# RFBoardLayoutGen0_v03_2JK2.net
KiCad netlist of a schematic drawn in EAGLE
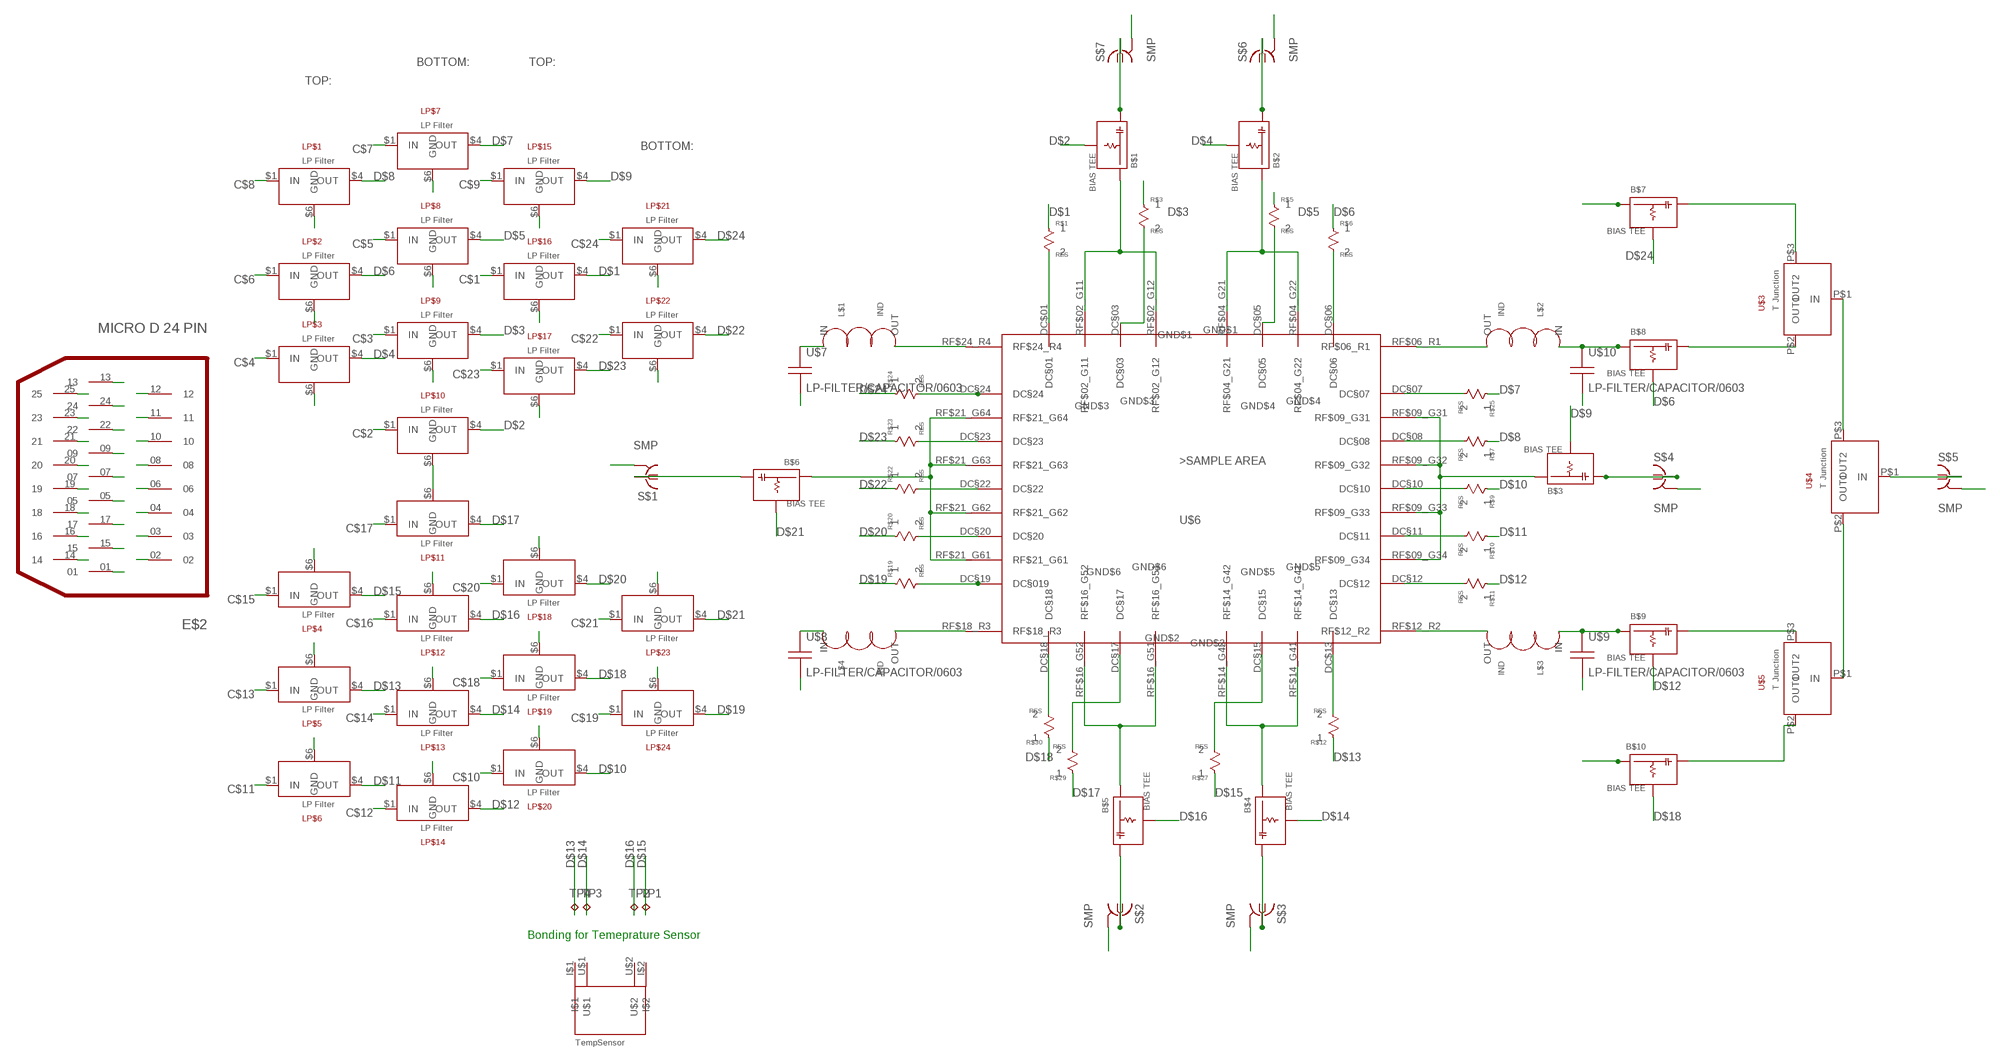
[diagram p0: schematic, sheet 1, part 1 of 2]
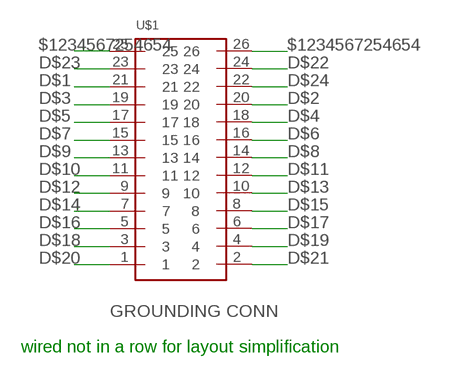
[diagram p1: schematic, sheet 1, part 2 of 2]

(export (version "E")
  (design (tool "Eeschema 10.0.6"))
  (components
    (comp (ref "B$1")
      (value "BIASTEEDOWN")
      (footprint "eagle-import:BIAS_TEE_DOWN_0603")
      (libsource (lib "eagle-import") (part "BIASTEEDOWN"))
    )
    (comp (ref "B$2")
      (value "BIASTEEUP")
      (footprint "eagle-import:BIAS_TEE_UP_0603")
      (libsource (lib "eagle-import") (part "BIASTEEUP"))
    )
    (comp (ref "B$3")
      (value "BIASTEEDOWN")
      (footprint "eagle-import:BIAS_TEE_DOWN_0603")
      (libsource (lib "eagle-import") (part "BIASTEEDOWN"))
    )
    (comp (ref "B$4")
      (value "BIASTEEDOWN")
      (footprint "eagle-import:BIAS_TEE_DOWN_0603")
      (libsource (lib "eagle-import") (part "BIASTEEDOWN"))
    )
    (comp (ref "B$5")
      (value "BIASTEEUP")
      (footprint "eagle-import:BIAS_TEE_UP_0603")
      (libsource (lib "eagle-import") (part "BIASTEEUP"))
    )
    (comp (ref "B$6")
      (value "BIASTEEDOWN")
      (footprint "eagle-import:BIAS_TEE_DOWN_0603")
      (libsource (lib "eagle-import") (part "BIASTEEDOWN"))
    )
    (comp (ref "B$7")
      (value "BIASTEEUP")
      (footprint "eagle-import:BIAS_TEE_UP_0603")
      (libsource (lib "eagle-import") (part "BIASTEEUP"))
    )
    (comp (ref "B$8")
      (value "BIASTEEDOWN")
      (footprint "eagle-import:BIAS_TEE_DOWN_0603")
      (libsource (lib "eagle-import") (part "BIASTEEDOWN"))
    )
    (comp (ref "B$9")
      (value "BIASTEEUP")
      (footprint "eagle-import:BIAS_TEE_UP_0603")
      (libsource (lib "eagle-import") (part "BIASTEEUP"))
    )
    (comp (ref "B$10")
      (value "BIASTEEDOWN")
      (footprint "eagle-import:BIAS_TEE_DOWN_0603")
      (libsource (lib "eagle-import") (part "BIASTEEDOWN"))
    )
    (comp (ref "E$2")
      (value "25_SOCKET_M83513(13-DPINOUT2")
      (footprint "eagle-import:25_SOCKET_M83513_13-D_V2")
      (libsource (lib "eagle-import") (part "25_SOCKET_M83513(13-DPINOUT2"))
    )
    (comp (ref "L$1")
      (value "L_MATCH")
      (footprint "eagle-import:L_MATCH")
      (libsource (lib "eagle-import") (part "L_MATCH"))
    )
    (comp (ref "L$2")
      (value "L_MATCH")
      (footprint "eagle-import:L_MATCH")
      (libsource (lib "eagle-import") (part "L_MATCH"))
    )
    (comp (ref "L$3")
      (value "L_MATCH")
      (footprint "eagle-import:L_MATCH")
      (libsource (lib "eagle-import") (part "L_MATCH"))
    )
    (comp (ref "L$4")
      (value "L_MATCH")
      (footprint "eagle-import:L_MATCH")
      (libsource (lib "eagle-import") (part "L_MATCH"))
    )
    (comp (ref "LP$1")
      (value "LP-FILTER/1-STAGETOP")
      (footprint "eagle-import:LP-FILTER_1_STAGE_OS_0603_TOP")
      (libsource (lib "eagle-import") (part "LP-FILTER/1-STAGETOP"))
    )
    (comp (ref "LP$2")
      (value "LP-FILTER/1-STAGETOP")
      (footprint "eagle-import:LP-FILTER_1_STAGE_OS_0603_TOP")
      (libsource (lib "eagle-import") (part "LP-FILTER/1-STAGETOP"))
    )
    (comp (ref "LP$3")
      (value "LP-FILTER/1-STAGETOP")
      (footprint "eagle-import:LP-FILTER_1_STAGE_OS_0603_TOP")
      (libsource (lib "eagle-import") (part "LP-FILTER/1-STAGETOP"))
    )
    (comp (ref "LP$4")
      (value "LP-FILTER/1-STAGETOP")
      (footprint "eagle-import:LP-FILTER_1_STAGE_OS_0603_TOP")
      (libsource (lib "eagle-import") (part "LP-FILTER/1-STAGETOP"))
    )
    (comp (ref "LP$5")
      (value "LP-FILTER/1-STAGETOP")
      (footprint "eagle-import:LP-FILTER_1_STAGE_OS_0603_TOP")
      (libsource (lib "eagle-import") (part "LP-FILTER/1-STAGETOP"))
    )
    (comp (ref "LP$6")
      (value "LP-FILTER/1-STAGETOP")
      (footprint "eagle-import:LP-FILTER_1_STAGE_OS_0603_TOP")
      (libsource (lib "eagle-import") (part "LP-FILTER/1-STAGETOP"))
    )
    (comp (ref "LP$7")
      (value "LP-FILTER/1-STAGEBOT")
      (footprint "eagle-import:LP-FILTER_1_STAGE_OS_0603_BOTTOM")
      (libsource (lib "eagle-import") (part "LP-FILTER/1-STAGEBOT"))
    )
    (comp (ref "LP$8")
      (value "LP-FILTER/1-STAGEBOT")
      (footprint "eagle-import:LP-FILTER_1_STAGE_OS_0603_BOTTOM")
      (libsource (lib "eagle-import") (part "LP-FILTER/1-STAGEBOT"))
    )
    (comp (ref "LP$9")
      (value "LP-FILTER/1-STAGEBOT")
      (footprint "eagle-import:LP-FILTER_1_STAGE_OS_0603_BOTTOM")
      (libsource (lib "eagle-import") (part "LP-FILTER/1-STAGEBOT"))
    )
    (comp (ref "LP$10")
      (value "LP-FILTER/1-STAGEBOT")
      (footprint "eagle-import:LP-FILTER_1_STAGE_OS_0603_BOTTOM")
      (libsource (lib "eagle-import") (part "LP-FILTER/1-STAGEBOT"))
    )
    (comp (ref "LP$11")
      (value "LP-FILTER/1-STAGEBOT")
      (footprint "eagle-import:LP-FILTER_1_STAGE_OS_0603_BOTTOM")
      (libsource (lib "eagle-import") (part "LP-FILTER/1-STAGEBOT"))
    )
    (comp (ref "LP$12")
      (value "LP-FILTER/1-STAGEBOT")
      (footprint "eagle-import:LP-FILTER_1_STAGE_OS_0603_BOTTOM")
      (libsource (lib "eagle-import") (part "LP-FILTER/1-STAGEBOT"))
    )
    (comp (ref "LP$13")
      (value "LP-FILTER/1-STAGEBOT")
      (footprint "eagle-import:LP-FILTER_1_STAGE_OS_0603_BOTTOM")
      (libsource (lib "eagle-import") (part "LP-FILTER/1-STAGEBOT"))
    )
    (comp (ref "LP$14")
      (value "LP-FILTER/1-STAGEBOT")
      (footprint "eagle-import:LP-FILTER_1_STAGE_OS_0603_BOTTOM")
      (libsource (lib "eagle-import") (part "LP-FILTER/1-STAGEBOT"))
    )
    (comp (ref "LP$15")
      (value "LP-FILTER/1-STAGETOP")
      (footprint "eagle-import:LP-FILTER_1_STAGE_OS_0603_TOP")
      (libsource (lib "eagle-import") (part "LP-FILTER/1-STAGETOP"))
    )
    (comp (ref "LP$16")
      (value "LP-FILTER/1-STAGETOP")
      (footprint "eagle-import:LP-FILTER_1_STAGE_OS_0603_TOP")
      (libsource (lib "eagle-import") (part "LP-FILTER/1-STAGETOP"))
    )
    (comp (ref "LP$17")
      (value "LP-FILTER/1-STAGETOP")
      (footprint "eagle-import:LP-FILTER_1_STAGE_OS_0603_TOP")
      (libsource (lib "eagle-import") (part "LP-FILTER/1-STAGETOP"))
    )
    (comp (ref "LP$18")
      (value "LP-FILTER/1-STAGETOP")
      (footprint "eagle-import:LP-FILTER_1_STAGE_OS_0603_TOP")
      (libsource (lib "eagle-import") (part "LP-FILTER/1-STAGETOP"))
    )
    (comp (ref "LP$19")
      (value "LP-FILTER/1-STAGETOP")
      (footprint "eagle-import:LP-FILTER_1_STAGE_OS_0603_TOP")
      (libsource (lib "eagle-import") (part "LP-FILTER/1-STAGETOP"))
    )
    (comp (ref "LP$20")
      (value "LP-FILTER/1-STAGETOP")
      (footprint "eagle-import:LP-FILTER_1_STAGE_OS_0603_TOP")
      (libsource (lib "eagle-import") (part "LP-FILTER/1-STAGETOP"))
    )
    (comp (ref "LP$21")
      (value "LP-FILTER/1-STAGEBOT")
      (footprint "eagle-import:LP-FILTER_1_STAGE_OS_0603_BOTTOM")
      (libsource (lib "eagle-import") (part "LP-FILTER/1-STAGEBOT"))
    )
    (comp (ref "LP$22")
      (value "LP-FILTER/1-STAGEBOT")
      (footprint "eagle-import:LP-FILTER_1_STAGE_OS_0603_BOTTOM")
      (libsource (lib "eagle-import") (part "LP-FILTER/1-STAGEBOT"))
    )
    (comp (ref "LP$23")
      (value "LP-FILTER/1-STAGEBOT")
      (footprint "eagle-import:LP-FILTER_1_STAGE_OS_0603_BOTTOM")
      (libsource (lib "eagle-import") (part "LP-FILTER/1-STAGEBOT"))
    )
    (comp (ref "LP$24")
      (value "LP-FILTER/1-STAGEBOT")
      (footprint "eagle-import:LP-FILTER_1_STAGE_OS_0603_BOTTOM")
      (libsource (lib "eagle-import") (part "LP-FILTER/1-STAGEBOT"))
    )
    (comp (ref "R$1")
      (value "10K")
      (footprint "eagle-import:LP-FILTER_RESISTOR_0603_BOTTOM")
      (libsource (lib "eagle-import") (part "LP-FILTER/RESISTOR/0603"))
    )
    (comp (ref "R$3")
      (value "10K")
      (footprint "eagle-import:LP-FILTER_RESISTOR_0603_BOTTOM")
      (libsource (lib "eagle-import") (part "LP-FILTER/RESISTOR/0603"))
    )
    (comp (ref "R$5")
      (value "10K")
      (footprint "eagle-import:LP-FILTER_RESISTOR_0603_BOTTOM")
      (libsource (lib "eagle-import") (part "LP-FILTER/RESISTOR/0603"))
    )
    (comp (ref "R$6")
      (value "10K")
      (footprint "eagle-import:LP-FILTER_RESISTOR_0603_BOTTOM")
      (libsource (lib "eagle-import") (part "LP-FILTER/RESISTOR/0603"))
    )
    (comp (ref "R$7")
      (value "10K")
      (footprint "eagle-import:LP-FILTER_RESISTOR_0603_BOTTOM")
      (libsource (lib "eagle-import") (part "LP-FILTER/RESISTOR/0603"))
    )
    (comp (ref "R$9")
      (value "10K")
      (footprint "eagle-import:LP-FILTER_RESISTOR_0603_BOTTOM")
      (libsource (lib "eagle-import") (part "LP-FILTER/RESISTOR/0603"))
    )
    (comp (ref "R$10")
      (value "10K")
      (footprint "eagle-import:LP-FILTER_RESISTOR_0603_BOTTOM")
      (libsource (lib "eagle-import") (part "LP-FILTER/RESISTOR/0603"))
    )
    (comp (ref "R$11")
      (value "10K")
      (footprint "eagle-import:LP-FILTER_RESISTOR_0603_BOTTOM")
      (libsource (lib "eagle-import") (part "LP-FILTER/RESISTOR/0603"))
    )
    (comp (ref "R$12")
      (value "10K")
      (footprint "eagle-import:LP-FILTER_RESISTOR_0603_BOTTOM")
      (libsource (lib "eagle-import") (part "LP-FILTER/RESISTOR/0603"))
    )
    (comp (ref "R$19")
      (value "10K")
      (footprint "eagle-import:LP-FILTER_RESISTOR_0603_BOTTOM")
      (libsource (lib "eagle-import") (part "LP-FILTER/RESISTOR/0603"))
    )
    (comp (ref "R$20")
      (value "10K")
      (footprint "eagle-import:LP-FILTER_RESISTOR_0603_BOTTOM")
      (libsource (lib "eagle-import") (part "LP-FILTER/RESISTOR/0603"))
    )
    (comp (ref "R$22")
      (value "10K")
      (footprint "eagle-import:LP-FILTER_RESISTOR_0603_BOTTOM")
      (libsource (lib "eagle-import") (part "LP-FILTER/RESISTOR/0603"))
    )
    (comp (ref "R$23")
      (value "10K")
      (footprint "eagle-import:LP-FILTER_RESISTOR_0603_BOTTOM")
      (libsource (lib "eagle-import") (part "LP-FILTER/RESISTOR/0603"))
    )
    (comp (ref "R$24")
      (value "10K")
      (footprint "eagle-import:LP-FILTER_RESISTOR_0603_BOTTOM")
      (libsource (lib "eagle-import") (part "LP-FILTER/RESISTOR/0603"))
    )
    (comp (ref "R$25")
      (value "10K")
      (footprint "eagle-import:LP-FILTER_RESISTOR_0603_BOTTOM")
      (libsource (lib "eagle-import") (part "LP-FILTER/RESISTOR/0603"))
    )
    (comp (ref "R$27")
      (value "10K")
      (footprint "eagle-import:LP-FILTER_RESISTOR_0603_BOTTOM")
      (libsource (lib "eagle-import") (part "LP-FILTER/RESISTOR/0603"))
    )
    (comp (ref "R$29")
      (value "10K")
      (footprint "eagle-import:LP-FILTER_RESISTOR_0603_BOTTOM")
      (libsource (lib "eagle-import") (part "LP-FILTER/RESISTOR/0603"))
    )
    (comp (ref "R$30")
      (value "10K")
      (footprint "eagle-import:LP-FILTER_RESISTOR_0603_BOTTOM")
      (libsource (lib "eagle-import") (part "LP-FILTER/RESISTOR/0603"))
    )
    (comp (ref "S$1")
      (value "MC-921WIDE")
      (footprint "eagle-import:SMP_STRAIGHT_MINI_WIDE")
      (libsource (lib "eagle-import") (part "MC-921WIDE"))
    )
    (comp (ref "S$2")
      (value "MC-921WIDE")
      (footprint "eagle-import:SMP_STRAIGHT_MINI_WIDE")
      (libsource (lib "eagle-import") (part "MC-921WIDE"))
    )
    (comp (ref "S$3")
      (value "MC-921WIDE")
      (footprint "eagle-import:SMP_STRAIGHT_MINI_WIDE")
      (libsource (lib "eagle-import") (part "MC-921WIDE"))
    )
    (comp (ref "S$4")
      (value "MC-921WIDE")
      (footprint "eagle-import:SMP_STRAIGHT_MINI_WIDE")
      (libsource (lib "eagle-import") (part "MC-921WIDE"))
    )
    (comp (ref "S$5")
      (value "MC-921WIDE")
      (footprint "eagle-import:SMP_STRAIGHT_MINI_WIDE")
      (libsource (lib "eagle-import") (part "MC-921WIDE"))
    )
    (comp (ref "S$6")
      (value "MC-921WIDE")
      (footprint "eagle-import:SMP_STRAIGHT_MINI_WIDE")
      (libsource (lib "eagle-import") (part "MC-921WIDE"))
    )
    (comp (ref "S$7")
      (value "MC-921WIDE")
      (footprint "eagle-import:SMP_STRAIGHT_MINI_WIDE")
      (libsource (lib "eagle-import") (part "MC-921WIDE"))
    )
    (comp (ref "TP1")
      (value "TPTP07SQ")
      (footprint "eagle-import:TP07SQ")
      (libsource (lib "eagle-import") (part "TPTP07SQ"))
    )
    (comp (ref "TP2")
      (value "TPTP07SQ")
      (footprint "eagle-import:TP07SQ")
      (libsource (lib "eagle-import") (part "TPTP07SQ"))
    )
    (comp (ref "TP3")
      (value "TPTP07SQ")
      (footprint "eagle-import:TP07SQ")
      (libsource (lib "eagle-import") (part "TPTP07SQ"))
    )
    (comp (ref "TP4")
      (value "TPTP07SQ")
      (footprint "eagle-import:TP07SQ")
      (libsource (lib "eagle-import") (part "TPTP07SQ"))
    )
    (comp (ref "U$1")
      (value "MEC8-113-02-L-D-RA1MBRD")
      (footprint "eagle-import:MEC8-113-02-L-D-RA1")
      (libsource (lib "eagle-import") (part "MEC8-113-02-L-D-RA1MBRD"))
    )
    (comp (ref "U$2")
      (value "TEMPSENS")
      (footprint "eagle-import:RX-BR_V1")
      (libsource (lib "eagle-import") (part "TEMPSENS"))
    )
    (comp (ref "U$3")
      (value "TJUNCTION")
      (footprint "eagle-import:T_JUNCTION_0.3MM")
      (libsource (lib "eagle-import") (part "TJUNCTION"))
    )
    (comp (ref "U$4")
      (value "TJUNCTION")
      (footprint "eagle-import:T_JUNCTION_0.3MM")
      (libsource (lib "eagle-import") (part "TJUNCTION"))
    )
    (comp (ref "U$5")
      (value "TJUNCTION")
      (footprint "eagle-import:T_JUNCTION_0.3MM")
      (libsource (lib "eagle-import") (part "TJUNCTION"))
    )
    (comp (ref "U$6")
      (value "24DC+10RF_V2.0")
      (footprint "eagle-import:24DC+10RF_400MU-PADS_0.7X0.7_V2.0")
      (libsource (lib "eagle-import") (part "24DC+10RF_V2.0"))
    )
    (comp (ref "U$7")
      (value "LP-FILTER/CAPACITOR/0603")
      (footprint "eagle-import:LP-FILTER_CAPACITOR_0603_BOTTOM")
      (libsource (lib "eagle-import") (part "LP-FILTER/CAPACITOR/0603"))
    )
    (comp (ref "U$8")
      (value "LP-FILTER/CAPACITOR/0603")
      (footprint "eagle-import:LP-FILTER_CAPACITOR_0603_BOTTOM")
      (libsource (lib "eagle-import") (part "LP-FILTER/CAPACITOR/0603"))
    )
    (comp (ref "U$9")
      (value "LP-FILTER/CAPACITOR/0603")
      (footprint "eagle-import:LP-FILTER_CAPACITOR_0603_BOTTOM")
      (libsource (lib "eagle-import") (part "LP-FILTER/CAPACITOR/0603"))
    )
    (comp (ref "U$10")
      (value "LP-FILTER/CAPACITOR/0603")
      (footprint "eagle-import:LP-FILTER_CAPACITOR_0603_BOTTOM")
      (libsource (lib "eagle-import") (part "LP-FILTER/CAPACITOR/0603"))
    )
  )
  (nets
    (net (code "1") (name "/$1234567254654") (class "Default")
      (node (ref "E$2") (pin "25") (pinfunction "25_25") (pintype "bidirectional"))
      (node (ref "LP$1") (pin "$6") (pinfunction "GND_$6") (pintype "bidirectional"))
      (node (ref "LP$10") (pin "$6") (pinfunction "GND_$6") (pintype "bidirectional"))
      (node (ref "LP$11") (pin "$6") (pinfunction "GND_$6") (pintype "bidirectional"))
      (node (ref "LP$12") (pin "$6") (pinfunction "GND_$6") (pintype "bidirectional"))
      (node (ref "LP$13") (pin "$6") (pinfunction "GND_$6") (pintype "bidirectional"))
      (node (ref "LP$14") (pin "$6") (pinfunction "GND_$6") (pintype "bidirectional"))
      (node (ref "LP$15") (pin "$6") (pinfunction "GND_$6") (pintype "bidirectional"))
      (node (ref "LP$16") (pin "$6") (pinfunction "GND_$6") (pintype "bidirectional"))
      (node (ref "LP$17") (pin "$6") (pinfunction "GND_$6") (pintype "bidirectional"))
      (node (ref "LP$18") (pin "$6") (pinfunction "GND_$6") (pintype "bidirectional"))
      (node (ref "LP$19") (pin "$6") (pinfunction "GND_$6") (pintype "bidirectional"))
      (node (ref "LP$2") (pin "$6") (pinfunction "GND_$6") (pintype "bidirectional"))
      (node (ref "LP$20") (pin "$6") (pinfunction "GND_$6") (pintype "bidirectional"))
      (node (ref "LP$21") (pin "$6") (pinfunction "GND_$6") (pintype "bidirectional"))
      (node (ref "LP$22") (pin "$6") (pinfunction "GND_$6") (pintype "bidirectional"))
      (node (ref "LP$23") (pin "$6") (pinfunction "GND_$6") (pintype "bidirectional"))
      (node (ref "LP$24") (pin "$6") (pinfunction "GND_$6") (pintype "bidirectional"))
      (node (ref "LP$3") (pin "$6") (pinfunction "GND_$6") (pintype "bidirectional"))
      (node (ref "LP$4") (pin "$6") (pinfunction "GND_$6") (pintype "bidirectional"))
      (node (ref "LP$5") (pin "$6") (pinfunction "GND_$6") (pintype "bidirectional"))
      (node (ref "LP$6") (pin "$6") (pinfunction "GND_$6") (pintype "bidirectional"))
      (node (ref "LP$7") (pin "$6") (pinfunction "GND_$6") (pintype "bidirectional"))
      (node (ref "LP$8") (pin "$6") (pinfunction "GND_$6") (pintype "bidirectional"))
      (node (ref "LP$9") (pin "$6") (pinfunction "GND_$6") (pintype "bidirectional"))
      (node (ref "S$1") (pin "2@1") (pinfunction "GND_2@1") (pintype "passive"))
      (node (ref "S$1") (pin "2@2") (pinfunction "GND_2@2") (pintype "passive"))
      (node (ref "S$2") (pin "2@1") (pinfunction "GND_2@1") (pintype "passive"))
      (node (ref "S$2") (pin "2@2") (pinfunction "GND_2@2") (pintype "passive"))
      (node (ref "S$3") (pin "2@1") (pinfunction "GND_2@1") (pintype "passive"))
      (node (ref "S$3") (pin "2@2") (pinfunction "GND_2@2") (pintype "passive"))
      (node (ref "S$4") (pin "2@1") (pinfunction "GND_2@1") (pintype "passive"))
      (node (ref "S$4") (pin "2@2") (pinfunction "GND_2@2") (pintype "passive"))
      (node (ref "S$5") (pin "2@1") (pinfunction "GND_2@1") (pintype "passive"))
      (node (ref "S$5") (pin "2@2") (pinfunction "GND_2@2") (pintype "passive"))
      (node (ref "S$6") (pin "2@1") (pinfunction "GND_2@1") (pintype "passive"))
      (node (ref "S$6") (pin "2@2") (pinfunction "GND_2@2") (pintype "passive"))
      (node (ref "S$7") (pin "2@1") (pinfunction "GND_2@1") (pintype "passive"))
      (node (ref "S$7") (pin "2@2") (pinfunction "GND_2@2") (pintype "passive"))
      (node (ref "U$1") (pin "25") (pinfunction "25_25") (pintype "bidirectional"))
      (node (ref "U$1") (pin "26") (pinfunction "26_26") (pintype "bidirectional"))
    )
    (net (code "2") (name "/C$1") (class "Default")
      (node (ref "E$2") (pin "01") (pinfunction "01_01") (pintype "bidirectional"))
      (node (ref "LP$16") (pin "$1") (pinfunction "IN_$1") (pintype "bidirectional"))
    )
    (net (code "3") (name "/C$2") (class "Default")
      (node (ref "E$2") (pin "02") (pinfunction "02_02") (pintype "bidirectional"))
      (node (ref "LP$10") (pin "$1") (pinfunction "IN_$1") (pintype "bidirectional"))
    )
    (net (code "4") (name "/C$3") (class "Default")
      (node (ref "E$2") (pin "03") (pinfunction "03_03") (pintype "bidirectional"))
      (node (ref "LP$9") (pin "$1") (pinfunction "IN_$1") (pintype "bidirectional"))
    )
    (net (code "5") (name "/C$4") (class "Default")
      (node (ref "E$2") (pin "04") (pinfunction "04_04") (pintype "bidirectional"))
      (node (ref "LP$3") (pin "$1") (pinfunction "IN_$1") (pintype "bidirectional"))
    )
    (net (code "6") (name "/C$5") (class "Default")
      (node (ref "E$2") (pin "05") (pinfunction "05_05") (pintype "bidirectional"))
      (node (ref "LP$8") (pin "$1") (pinfunction "IN_$1") (pintype "bidirectional"))
    )
    (net (code "7") (name "/C$6") (class "Default")
      (node (ref "E$2") (pin "06") (pinfunction "06_06") (pintype "bidirectional"))
      (node (ref "LP$2") (pin "$1") (pinfunction "IN_$1") (pintype "bidirectional"))
    )
    (net (code "8") (name "/C$7") (class "Default")
      (node (ref "E$2") (pin "07") (pinfunction "07_07") (pintype "bidirectional"))
      (node (ref "LP$7") (pin "$1") (pinfunction "IN_$1") (pintype "bidirectional"))
    )
    (net (code "9") (name "/C$8") (class "Default")
      (node (ref "E$2") (pin "08") (pinfunction "08_08") (pintype "bidirectional"))
      (node (ref "LP$1") (pin "$1") (pinfunction "IN_$1") (pintype "bidirectional"))
    )
    (net (code "10") (name "/C$9") (class "Default")
      (node (ref "E$2") (pin "09") (pinfunction "09_09") (pintype "bidirectional"))
      (node (ref "LP$15") (pin "$1") (pinfunction "IN_$1") (pintype "bidirectional"))
    )
    (net (code "11") (name "/C$10") (class "Default")
      (node (ref "E$2") (pin "10") (pinfunction "10_10") (pintype "bidirectional"))
      (node (ref "LP$20") (pin "$1") (pinfunction "IN_$1") (pintype "bidirectional"))
    )
    (net (code "12") (name "/C$11") (class "Default")
      (node (ref "E$2") (pin "11") (pinfunction "11_11") (pintype "bidirectional"))
      (node (ref "LP$6") (pin "$1") (pinfunction "IN_$1") (pintype "bidirectional"))
    )
    (net (code "13") (name "/C$12") (class "Default")
      (node (ref "E$2") (pin "12") (pinfunction "12_12") (pintype "bidirectional"))
      (node (ref "LP$14") (pin "$1") (pinfunction "IN_$1") (pintype "bidirectional"))
    )
    (net (code "14") (name "/C$13") (class "Default")
      (node (ref "E$2") (pin "13") (pinfunction "13_13") (pintype "bidirectional"))
      (node (ref "LP$5") (pin "$1") (pinfunction "IN_$1") (pintype "bidirectional"))
    )
    (net (code "15") (name "/C$14") (class "Default")
      (node (ref "E$2") (pin "14") (pinfunction "14_14") (pintype "bidirectional"))
      (node (ref "LP$13") (pin "$1") (pinfunction "IN_$1") (pintype "bidirectional"))
    )
    (net (code "16") (name "/C$15") (class "Default")
      (node (ref "E$2") (pin "15") (pinfunction "15_15") (pintype "bidirectional"))
      (node (ref "LP$4") (pin "$1") (pinfunction "IN_$1") (pintype "bidirectional"))
    )
    (net (code "17") (name "/C$16") (class "Default")
      (node (ref "E$2") (pin "16") (pinfunction "16_16") (pintype "bidirectional"))
      (node (ref "LP$12") (pin "$1") (pinfunction "IN_$1") (pintype "bidirectional"))
    )
    (net (code "18") (name "/C$17") (class "Default")
      (node (ref "E$2") (pin "17") (pinfunction "17_17") (pintype "bidirectional"))
      (node (ref "LP$11") (pin "$1") (pinfunction "IN_$1") (pintype "bidirectional"))
    )
    (net (code "19") (name "/C$18") (class "Default")
      (node (ref "E$2") (pin "18") (pinfunction "18_18") (pintype "bidirectional"))
      (node (ref "LP$19") (pin "$1") (pinfunction "IN_$1") (pintype "bidirectional"))
    )
    (net (code "20") (name "/C$19") (class "Default")
      (node (ref "E$2") (pin "19") (pinfunction "19_19") (pintype "bidirectional"))
      (node (ref "LP$24") (pin "$1") (pinfunction "IN_$1") (pintype "bidirectional"))
    )
    (net (code "21") (name "/C$20") (class "Default")
      (node (ref "E$2") (pin "20") (pinfunction "20_20") (pintype "bidirectional"))
      (node (ref "LP$18") (pin "$1") (pinfunction "IN_$1") (pintype "bidirectional"))
    )
    (net (code "22") (name "/C$21") (class "Default")
      (node (ref "E$2") (pin "21") (pinfunction "21_21") (pintype "bidirectional"))
      (node (ref "LP$23") (pin "$1") (pinfunction "IN_$1") (pintype "bidirectional"))
    )
    (net (code "23") (name "/C$22") (class "Default")
      (node (ref "E$2") (pin "22") (pinfunction "22_22") (pintype "bidirectional"))
      (node (ref "LP$22") (pin "$1") (pinfunction "IN_$1") (pintype "bidirectional"))
    )
    (net (code "24") (name "/C$23") (class "Default")
      (node (ref "E$2") (pin "23") (pinfunction "23_23") (pintype "bidirectional"))
      (node (ref "LP$17") (pin "$1") (pinfunction "IN_$1") (pintype "bidirectional"))
    )
    (net (code "25") (name "/C$24") (class "Default")
      (node (ref "E$2") (pin "24") (pinfunction "24_24") (pintype "bidirectional"))
      (node (ref "LP$21") (pin "$1") (pinfunction "IN_$1") (pintype "bidirectional"))
    )
    (net (code "26") (name "/D$1") (class "Default")
      (node (ref "LP$16") (pin "$4") (pinfunction "OUT_$4") (pintype "bidirectional"))
      (node (ref "R$1") (pin "IN") (pinfunction "1_IN") (pintype "passive"))
      (node (ref "U$1") (pin "21") (pinfunction "21_21") (pintype "bidirectional"))
    )
    (net (code "27") (name "/D$2") (class "Default")
      (node (ref "B$1") (pin "LF") (pinfunction "LF_LF") (pintype "bidirectional"))
      (node (ref "LP$10") (pin "$4") (pinfunction "OUT_$4") (pintype "bidirectional"))
      (node (ref "U$1") (pin "20") (pinfunction "20_20") (pintype "bidirectional"))
    )
    (net (code "28") (name "/D$3") (class "Default")
      (node (ref "LP$9") (pin "$4") (pinfunction "OUT_$4") (pintype "bidirectional"))
      (node (ref "R$3") (pin "IN") (pinfunction "1_IN") (pintype "passive"))
      (node (ref "U$1") (pin "19") (pinfunction "19_19") (pintype "bidirectional"))
    )
    (net (code "29") (name "/D$4") (class "Default")
      (node (ref "B$2") (pin "LF") (pinfunction "LF_LF") (pintype "bidirectional"))
      (node (ref "LP$3") (pin "$4") (pinfunction "OUT_$4") (pintype "bidirectional"))
      (node (ref "U$1") (pin "18") (pinfunction "18_18") (pintype "bidirectional"))
    )
    (net (code "30") (name "/D$5") (class "Default")
      (node (ref "LP$8") (pin "$4") (pinfunction "OUT_$4") (pintype "bidirectional"))
      (node (ref "R$5") (pin "IN") (pinfunction "1_IN") (pintype "passive"))
      (node (ref "U$1") (pin "17") (pinfunction "17_17") (pintype "bidirectional"))
    )
    (net (code "31") (name "/D$6") (class "Default")
      (node (ref "B$8") (pin "LF") (pinfunction "LF_LF") (pintype "bidirectional"))
      (node (ref "LP$2") (pin "$4") (pinfunction "OUT_$4") (pintype "bidirectional"))
      (node (ref "R$6") (pin "IN") (pinfunction "1_IN") (pintype "passive"))
      (node (ref "U$1") (pin "16") (pinfunction "16_16") (pintype "bidirectional"))
    )
    (net (code "32") (name "/D$7") (class "Default")
      (node (ref "LP$7") (pin "$4") (pinfunction "OUT_$4") (pintype "bidirectional"))
      (node (ref "R$25") (pin "IN") (pinfunction "1_IN") (pintype "passive"))
      (node (ref "U$1") (pin "15") (pinfunction "15_15") (pintype "bidirectional"))
    )
    (net (code "33") (name "/D$8") (class "Default")
      (node (ref "LP$1") (pin "$4") (pinfunction "OUT_$4") (pintype "bidirectional"))
      (node (ref "R$7") (pin "IN") (pinfunction "1_IN") (pintype "passive"))
      (node (ref "U$1") (pin "14") (pinfunction "14_14") (pintype "bidirectional"))
    )
    (net (code "34") (name "/D$9") (class "Default")
      (node (ref "B$3") (pin "LF") (pinfunction "LF_LF") (pintype "bidirectional"))
      (node (ref "LP$15") (pin "$4") (pinfunction "OUT_$4") (pintype "bidirectional"))
      (node (ref "U$1") (pin "13") (pinfunction "13_13") (pintype "bidirectional"))
    )
    (net (code "35") (name "/D$10") (class "Default")
      (node (ref "LP$20") (pin "$4") (pinfunction "OUT_$4") (pintype "bidirectional"))
      (node (ref "R$9") (pin "IN") (pinfunction "1_IN") (pintype "passive"))
      (node (ref "U$1") (pin "11") (pinfunction "11_11") (pintype "bidirectional"))
    )
    (net (code "36") (name "/D$11") (class "Default")
      (node (ref "LP$6") (pin "$4") (pinfunction "OUT_$4") (pintype "bidirectional"))
      (node (ref "R$10") (pin "IN") (pinfunction "1_IN") (pintype "passive"))
      (node (ref "U$1") (pin "12") (pinfunction "12_12") (pintype "bidirectional"))
    )
    (net (code "37") (name "/D$12") (class "Default")
      (node (ref "B$9") (pin "LF") (pinfunction "LF_LF") (pintype "bidirectional"))
      (node (ref "LP$14") (pin "$4") (pinfunction "OUT_$4") (pintype "bidirectional"))
      (node (ref "R$11") (pin "IN") (pinfunction "1_IN") (pintype "passive"))
      (node (ref "U$1") (pin "9") (pinfunction "9_9") (pintype "bidirectional"))
    )
    (net (code "38") (name "/D$13") (class "Default")
      (node (ref "LP$5") (pin "$4") (pinfunction "OUT_$4") (pintype "bidirectional"))
      (node (ref "R$12") (pin "IN") (pinfunction "1_IN") (pintype "passive"))
      (node (ref "TP4") (pin "TP") (pinfunction "TP_TP") (pintype "input"))
      (node (ref "U$1") (pin "10") (pinfunction "10_10") (pintype "bidirectional"))
    )
    (net (code "39") (name "/D$14") (class "Default")
      (node (ref "B$4") (pin "LF") (pinfunction "LF_LF") (pintype "bidirectional"))
      (node (ref "LP$13") (pin "$4") (pinfunction "OUT_$4") (pintype "bidirectional"))
      (node (ref "TP3") (pin "TP") (pinfunction "TP_TP") (pintype "input"))
      (node (ref "U$1") (pin "7") (pinfunction "7_7") (pintype "bidirectional"))
    )
    (net (code "40") (name "/D$15") (class "Default")
      (node (ref "LP$4") (pin "$4") (pinfunction "OUT_$4") (pintype "bidirectional"))
      (node (ref "R$27") (pin "IN") (pinfunction "1_IN") (pintype "passive"))
      (node (ref "TP1") (pin "TP") (pinfunction "TP_TP") (pintype "input"))
      (node (ref "U$1") (pin "8") (pinfunction "8_8") (pintype "bidirectional"))
    )
    (net (code "41") (name "/D$16") (class "Default")
      (node (ref "B$5") (pin "LF") (pinfunction "LF_LF") (pintype "bidirectional"))
      (node (ref "LP$12") (pin "$4") (pinfunction "OUT_$4") (pintype "bidirectional"))
      (node (ref "TP2") (pin "TP") (pinfunction "TP_TP") (pintype "input"))
      (node (ref "U$1") (pin "5") (pinfunction "5_5") (pintype "bidirectional"))
    )
    (net (code "42") (name "/D$17") (class "Default")
      (node (ref "LP$11") (pin "$4") (pinfunction "OUT_$4") (pintype "bidirectional"))
      (node (ref "R$29") (pin "IN") (pinfunction "1_IN") (pintype "passive"))
      (node (ref "U$1") (pin "6") (pinfunction "6_6") (pintype "bidirectional"))
    )
    (net (code "43") (name "/D$18") (class "Default")
      (node (ref "B$10") (pin "LF") (pinfunction "LF_LF") (pintype "bidirectional"))
      (node (ref "LP$19") (pin "$4") (pinfunction "OUT_$4") (pintype "bidirectional"))
      (node (ref "R$30") (pin "IN") (pinfunction "1_IN") (pintype "passive"))
      (node (ref "U$1") (pin "3") (pinfunction "3_3") (pintype "bidirectional"))
    )
    (net (code "44") (name "/D$19") (class "Default")
      (node (ref "LP$24") (pin "$4") (pinfunction "OUT_$4") (pintype "bidirectional"))
      (node (ref "R$19") (pin "IN") (pinfunction "1_IN") (pintype "passive"))
      (node (ref "U$1") (pin "4") (pinfunction "4_4") (pintype "bidirectional"))
    )
    (net (code "45") (name "/D$20") (class "Default")
      (node (ref "LP$18") (pin "$4") (pinfunction "OUT_$4") (pintype "bidirectional"))
      (node (ref "R$20") (pin "IN") (pinfunction "1_IN") (pintype "passive"))
      (node (ref "U$1") (pin "1") (pinfunction "1_1") (pintype "bidirectional"))
    )
    (net (code "46") (name "/D$21") (class "Default")
      (node (ref "B$6") (pin "LF") (pinfunction "LF_LF") (pintype "bidirectional"))
      (node (ref "LP$23") (pin "$4") (pinfunction "OUT_$4") (pintype "bidirectional"))
      (node (ref "U$1") (pin "2") (pinfunction "2_2") (pintype "bidirectional"))
    )
    (net (code "47") (name "/D$22") (class "Default")
      (node (ref "LP$22") (pin "$4") (pinfunction "OUT_$4") (pintype "bidirectional"))
      (node (ref "R$22") (pin "IN") (pinfunction "1_IN") (pintype "passive"))
      (node (ref "U$1") (pin "24") (pinfunction "24_24") (pintype "bidirectional"))
    )
    (net (code "48") (name "/D$23") (class "Default")
      (node (ref "LP$17") (pin "$4") (pinfunction "OUT_$4") (pintype "bidirectional"))
      (node (ref "R$23") (pin "IN") (pinfunction "1_IN") (pintype "passive"))
      (node (ref "U$1") (pin "23") (pinfunction "23_23") (pintype "bidirectional"))
    )
    (net (code "49") (name "/D$24") (class "Default")
      (node (ref "B$7") (pin "LF") (pinfunction "LF_LF") (pintype "bidirectional"))
      (node (ref "LP$21") (pin "$4") (pinfunction "OUT_$4") (pintype "bidirectional"))
      (node (ref "R$24") (pin "IN") (pinfunction "1_IN") (pintype "passive"))
      (node (ref "U$1") (pin "22") (pinfunction "22_22") (pintype "bidirectional"))
    )
    (net (code "50") (name "/GND") (class "Default")
      (node (ref "U$10") (pin "OUT") (pinfunction "2_OUT") (pintype "passive"))
      (node (ref "U$7") (pin "OUT") (pinfunction "2_OUT") (pintype "passive"))
      (node (ref "U$8") (pin "OUT") (pinfunction "2_OUT") (pintype "passive"))
      (node (ref "U$9") (pin "OUT") (pinfunction "2_OUT") (pintype "passive"))
    )
    (net (code "51") (name "/RF$3") (class "Default")
      (node (ref "B$10") (pin "OUT") (pinfunction "OUT_OUT") (pintype "bidirectional"))
      (node (ref "L$4") (pin "IN") (pinfunction "IN_IN") (pintype "passive"))
      (node (ref "U$8") (pin "IN") (pinfunction "1_IN") (pintype "passive"))
    )
    (net (code "52") (name "/RF$4") (class "Default")
      (node (ref "B$7") (pin "OUT") (pinfunction "OUT_OUT") (pintype "bidirectional"))
      (node (ref "L$1") (pin "IN") (pinfunction "IN_IN") (pintype "passive"))
      (node (ref "U$7") (pin "IN") (pinfunction "1_IN") (pintype "passive"))
    )
    (net (code "53") (name "Net-(B$1-PadHF)") (class "Default")
      (node (ref "B$1") (pin "HF") (pinfunction "HF_HF") (pintype "bidirectional"))
      (node (ref "S$7") (pin "1") (pinfunction "1_1") (pintype "passive"))
    )
    (net (code "54") (name "Net-(B$1-PadOUT)") (class "Default")
      (node (ref "B$1") (pin "OUT") (pinfunction "OUT_OUT") (pintype "bidirectional"))
      (node (ref "U$6") (pin "RF$02_G11") (pinfunction "RF$02_G11_RF$02_G11") (pintype "bidirectional"))
      (node (ref "U$6") (pin "RF$02_G12") (pinfunction "RF$02_G12_RF$02_G12") (pintype "bidirectional"))
    )
    (net (code "55") (name "Net-(B$2-PadHF)") (class "Default")
      (node (ref "B$2") (pin "HF") (pinfunction "HF_HF") (pintype "bidirectional"))
      (node (ref "S$6") (pin "1") (pinfunction "1_1") (pintype "passive"))
    )
    (net (code "56") (name "Net-(B$2-PadOUT)") (class "Default")
      (node (ref "B$2") (pin "OUT") (pinfunction "OUT_OUT") (pintype "bidirectional"))
      (node (ref "U$6") (pin "RF$04_G21") (pinfunction "RF$04_G21_RF$04_G21") (pintype "bidirectional"))
      (node (ref "U$6") (pin "RF$04_G22") (pinfunction "RF$04_G22_RF$04_G22") (pintype "bidirectional"))
    )
    (net (code "57") (name "Net-(B$3-PadHF)") (class "Default")
      (node (ref "B$3") (pin "HF") (pinfunction "HF_HF") (pintype "bidirectional"))
      (node (ref "S$4") (pin "1") (pinfunction "1_1") (pintype "passive"))
    )
    (net (code "58") (name "Net-(B$3-PadOUT)") (class "Default")
      (node (ref "B$3") (pin "OUT") (pinfunction "OUT_OUT") (pintype "bidirectional"))
      (node (ref "U$6") (pin "RF$09_G31") (pinfunction "RF$09_G31_RF$09_G31") (pintype "bidirectional"))
      (node (ref "U$6") (pin "RF$09_G32") (pinfunction "RF$09_G32_RF$09_G32") (pintype "bidirectional"))
      (node (ref "U$6") (pin "RF$09_G33") (pinfunction "RF$09_G33_RF$09_G33") (pintype "bidirectional"))
      (node (ref "U$6") (pin "RF$09_G34") (pinfunction "RF$09_G34_RF$09_G34") (pintype "bidirectional"))
    )
    (net (code "59") (name "Net-(B$4-PadHF)") (class "Default")
      (node (ref "B$4") (pin "HF") (pinfunction "HF_HF") (pintype "bidirectional"))
      (node (ref "S$3") (pin "1") (pinfunction "1_1") (pintype "passive"))
    )
    (net (code "60") (name "Net-(B$4-PadOUT)") (class "Default")
      (node (ref "B$4") (pin "OUT") (pinfunction "OUT_OUT") (pintype "bidirectional"))
      (node (ref "U$6") (pin "RF$14_G41") (pinfunction "RF$14_G41_RF$14_G41") (pintype "bidirectional"))
      (node (ref "U$6") (pin "RF$14_G42") (pinfunction "RF$14_G42_RF$14_G42") (pintype "bidirectional"))
    )
    (net (code "61") (name "Net-(B$5-PadHF)") (class "Default")
      (node (ref "B$5") (pin "HF") (pinfunction "HF_HF") (pintype "bidirectional"))
      (node (ref "S$2") (pin "1") (pinfunction "1_1") (pintype "passive"))
    )
    (net (code "62") (name "Net-(B$5-PadOUT)") (class "Default")
      (node (ref "B$5") (pin "OUT") (pinfunction "OUT_OUT") (pintype "bidirectional"))
      (node (ref "U$6") (pin "RF$16_G51") (pinfunction "RF$16_G51_RF$16_G51") (pintype "bidirectional"))
      (node (ref "U$6") (pin "RF$16_G52") (pinfunction "RF$16_G52_RF$16_G52") (pintype "bidirectional"))
    )
    (net (code "63") (name "Net-(B$6-PadHF)") (class "Default")
      (node (ref "B$6") (pin "HF") (pinfunction "HF_HF") (pintype "bidirectional"))
      (node (ref "S$1") (pin "1") (pinfunction "1_1") (pintype "passive"))
    )
    (net (code "64") (name "Net-(B$6-PadOUT)") (class "Default")
      (node (ref "B$6") (pin "OUT") (pinfunction "OUT_OUT") (pintype "bidirectional"))
      (node (ref "U$6") (pin "RF$21_G61") (pinfunction "RF$21_G61_RF$21_G61") (pintype "bidirectional"))
      (node (ref "U$6") (pin "RF$21_G62") (pinfunction "RF$21_G62_RF$21_G62") (pintype "bidirectional"))
      (node (ref "U$6") (pin "RF$21_G63") (pinfunction "RF$21_G63_RF$21_G63") (pintype "bidirectional"))
      (node (ref "U$6") (pin "RF$21_G64") (pinfunction "RF$21_G64_RF$21_G64") (pintype "bidirectional"))
    )
    (net (code "65") (name "Net-(L$1-PadOUT)") (class "Default")
      (node (ref "L$1") (pin "OUT") (pinfunction "OUT_OUT") (pintype "passive"))
      (node (ref "U$6") (pin "RF$24_R4") (pinfunction "RF$24_R4_RF$24_R4") (pintype "bidirectional"))
    )
    (net (code "66") (name "Net-(L$2-PadOUT)") (class "Default")
      (node (ref "L$2") (pin "OUT") (pinfunction "OUT_OUT") (pintype "passive"))
      (node (ref "U$6") (pin "RF$06_R1") (pinfunction "RF$06_R1_RF$06_R1") (pintype "bidirectional"))
    )
    (net (code "67") (name "Net-(L$3-PadOUT)") (class "Default")
      (node (ref "L$3") (pin "OUT") (pinfunction "OUT_OUT") (pintype "passive"))
      (node (ref "U$6") (pin "RF$12_R2") (pinfunction "RF$12_R2_RF$12_R2") (pintype "bidirectional"))
    )
    (net (code "68") (name "Net-(L$4-PadOUT)") (class "Default")
      (node (ref "L$4") (pin "OUT") (pinfunction "OUT_OUT") (pintype "passive"))
      (node (ref "U$6") (pin "RF$18_R3") (pinfunction "RF$18_R3_RF$18_R3") (pintype "bidirectional"))
    )
    (net (code "69") (name "Net-(R$1-2)") (class "Default")
      (node (ref "R$1") (pin "OUT") (pinfunction "2_OUT") (pintype "passive"))
      (node (ref "U$6") (pin "DC$01") (pinfunction "DC§01_DC$01") (pintype "bidirectional"))
    )
    (net (code "70") (name "Net-(R$3-2)") (class "Default")
      (node (ref "R$3") (pin "OUT") (pinfunction "2_OUT") (pintype "passive"))
      (node (ref "U$6") (pin "DC§03") (pinfunction "DC§03_DC§03") (pintype "bidirectional"))
    )
    (net (code "71") (name "Net-(R$5-2)") (class "Default")
      (node (ref "R$5") (pin "OUT") (pinfunction "2_OUT") (pintype "passive"))
      (node (ref "U$6") (pin "DC§05") (pinfunction "DC§05_DC§05") (pintype "bidirectional"))
    )
    (net (code "72") (name "Net-(R$6-2)") (class "Default")
      (node (ref "R$6") (pin "OUT") (pinfunction "2_OUT") (pintype "passive"))
      (node (ref "U$6") (pin "DC§06") (pinfunction "DC§06_DC§06") (pintype "bidirectional"))
    )
    (net (code "73") (name "Net-(R$7-2)") (class "Default")
      (node (ref "R$7") (pin "OUT") (pinfunction "2_OUT") (pintype "passive"))
      (node (ref "U$6") (pin "DC§08") (pinfunction "DC§08_DC§08") (pintype "bidirectional"))
    )
    (net (code "74") (name "Net-(R$9-2)") (class "Default")
      (node (ref "R$9") (pin "OUT") (pinfunction "2_OUT") (pintype "passive"))
      (node (ref "U$6") (pin "DC§10") (pinfunction "DC§10_DC§10") (pintype "bidirectional"))
    )
    (net (code "75") (name "Net-(R$10-2)") (class "Default")
      (node (ref "R$10") (pin "OUT") (pinfunction "2_OUT") (pintype "passive"))
      (node (ref "U$6") (pin "DC§11") (pinfunction "DC§11_DC§11") (pintype "bidirectional"))
    )
    (net (code "76") (name "Net-(R$11-2)") (class "Default")
      (node (ref "R$11") (pin "OUT") (pinfunction "2_OUT") (pintype "passive"))
      (node (ref "U$6") (pin "DC§12") (pinfunction "DC§12_DC§12") (pintype "bidirectional"))
    )
    (net (code "77") (name "Net-(R$12-2)") (class "Default")
      (node (ref "R$12") (pin "OUT") (pinfunction "2_OUT") (pintype "passive"))
      (node (ref "U$6") (pin "DC$13") (pinfunction "DC§13_DC$13") (pintype "bidirectional"))
    )
    (net (code "78") (name "Net-(R$19-2)") (class "Default")
      (node (ref "R$19") (pin "OUT") (pinfunction "2_OUT") (pintype "passive"))
      (node (ref "U$6") (pin "DC§19") (pinfunction "DC§019_DC§19") (pintype "bidirectional"))
    )
    (net (code "79") (name "Net-(R$20-2)") (class "Default")
      (node (ref "R$20") (pin "OUT") (pinfunction "2_OUT") (pintype "passive"))
      (node (ref "U$6") (pin "DC§20") (pinfunction "DC§20_DC§20") (pintype "bidirectional"))
    )
    (net (code "80") (name "Net-(R$22-2)") (class "Default")
      (node (ref "R$22") (pin "OUT") (pinfunction "2_OUT") (pintype "passive"))
      (node (ref "U$6") (pin "DC§22") (pinfunction "DC§22_DC§22") (pintype "bidirectional"))
    )
    (net (code "81") (name "Net-(R$23-2)") (class "Default")
      (node (ref "R$23") (pin "OUT") (pinfunction "2_OUT") (pintype "passive"))
      (node (ref "U$6") (pin "DC§23") (pinfunction "DC§23_DC§23") (pintype "bidirectional"))
    )
    (net (code "82") (name "Net-(R$24-2)") (class "Default")
      (node (ref "R$24") (pin "OUT") (pinfunction "2_OUT") (pintype "passive"))
      (node (ref "U$6") (pin "DC§24") (pinfunction "DC§24_DC§24") (pintype "bidirectional"))
    )
    (net (code "83") (name "Net-(R$25-2)") (class "Default")
      (node (ref "R$25") (pin "OUT") (pinfunction "2_OUT") (pintype "passive"))
      (node (ref "U$6") (pin "DC§07") (pinfunction "DC§07_DC§07") (pintype "bidirectional"))
    )
    (net (code "84") (name "Net-(R$27-2)") (class "Default")
      (node (ref "R$27") (pin "OUT") (pinfunction "2_OUT") (pintype "passive"))
      (node (ref "U$6") (pin "DC§15") (pinfunction "DC§15_DC§15") (pintype "bidirectional"))
    )
    (net (code "85") (name "Net-(R$29-2)") (class "Default")
      (node (ref "R$29") (pin "OUT") (pinfunction "2_OUT") (pintype "passive"))
      (node (ref "U$6") (pin "DC§17") (pinfunction "DC§17_DC§17") (pintype "bidirectional"))
    )
    (net (code "86") (name "Net-(R$30-2)") (class "Default")
      (node (ref "R$30") (pin "OUT") (pinfunction "2_OUT") (pintype "passive"))
      (node (ref "U$6") (pin "DC§18") (pinfunction "DC§18_DC§18") (pintype "bidirectional"))
    )
    (net (code "87") (name "Net-(U$3-IN)") (class "Default")
      (node (ref "U$3") (pin "P$1") (pinfunction "IN_P$1") (pintype "bidirectional"))
      (node (ref "U$4") (pin "P$3") (pinfunction "OUT2_P$3") (pintype "bidirectional"))
    )
    (net (code "88") (name "Net-(U$3-OUT1)") (class "Default")
      (node (ref "B$8") (pin "HF") (pinfunction "HF_HF") (pintype "bidirectional"))
      (node (ref "U$3") (pin "P$2") (pinfunction "OUT1_P$2") (pintype "bidirectional"))
    )
    (net (code "89") (name "Net-(U$3-OUT2)") (class "Default")
      (node (ref "B$7") (pin "HF") (pinfunction "HF_HF") (pintype "bidirectional"))
      (node (ref "U$3") (pin "P$3") (pinfunction "OUT2_P$3") (pintype "bidirectional"))
    )
    (net (code "90") (name "Net-(U$4-IN)") (class "Default")
      (node (ref "S$5") (pin "1") (pinfunction "1_1") (pintype "passive"))
      (node (ref "U$4") (pin "P$1") (pinfunction "IN_P$1") (pintype "bidirectional"))
    )
    (net (code "91") (name "Net-(U$4-OUT1)") (class "Default")
      (node (ref "U$4") (pin "P$2") (pinfunction "OUT1_P$2") (pintype "bidirectional"))
      (node (ref "U$5") (pin "P$1") (pinfunction "IN_P$1") (pintype "bidirectional"))
    )
    (net (code "92") (name "Net-(U$5-OUT1)") (class "Default")
      (node (ref "B$10") (pin "HF") (pinfunction "HF_HF") (pintype "bidirectional"))
      (node (ref "U$5") (pin "P$2") (pinfunction "OUT1_P$2") (pintype "bidirectional"))
    )
    (net (code "93") (name "Net-(U$5-OUT2)") (class "Default")
      (node (ref "B$9") (pin "HF") (pinfunction "HF_HF") (pintype "bidirectional"))
      (node (ref "U$5") (pin "P$3") (pinfunction "OUT2_P$3") (pintype "bidirectional"))
    )
    (net (code "94") (name "Net-(U$9-1)") (class "Default")
      (node (ref "B$9") (pin "OUT") (pinfunction "OUT_OUT") (pintype "bidirectional"))
      (node (ref "L$3") (pin "IN") (pinfunction "IN_IN") (pintype "passive"))
      (node (ref "U$9") (pin "IN") (pinfunction "1_IN") (pintype "passive"))
    )
    (net (code "95") (name "Net-(U$10-1)") (class "Default")
      (node (ref "B$8") (pin "OUT") (pinfunction "OUT_OUT") (pintype "bidirectional"))
      (node (ref "L$2") (pin "IN") (pinfunction "IN_IN") (pintype "passive"))
      (node (ref "U$10") (pin "IN") (pinfunction "1_IN") (pintype "passive"))
    )
    (net (code "96") (name "unconnected-(U$2-PadI$1)") (class "Default")
      (node (ref "U$2") (pin "I$1") (pinfunction "I$1_I$1") (pintype "bidirectional"))
    )
    (net (code "97") (name "unconnected-(U$2-PadI$2)") (class "Default")
      (node (ref "U$2") (pin "I$2") (pinfunction "I$2_I$2") (pintype "bidirectional"))
    )
    (net (code "98") (name "unconnected-(U$2-PadU$1)") (class "Default")
      (node (ref "U$2") (pin "U$1") (pinfunction "U$1_U$1") (pintype "bidirectional"))
    )
    (net (code "99") (name "unconnected-(U$2-PadU$2)") (class "Default")
      (node (ref "U$2") (pin "U$2") (pinfunction "U$2_U$2") (pintype "bidirectional"))
    )
    (net (code "100") (name "unconnected-(U$6-PadGND$1)") (class "Default")
      (node (ref "U$6") (pin "GND$1") (pinfunction "GND$1_GND$1") (pintype "bidirectional"))
    )
    (net (code "101") (name "unconnected-(U$6-PadGND$2)") (class "Default")
      (node (ref "U$6") (pin "GND$2") (pinfunction "GND$2_GND$2") (pintype "bidirectional"))
    )
    (net (code "102") (name "unconnected-(U$6-PadGND$3)") (class "Default")
      (node (ref "U$6") (pin "GND$3") (pinfunction "GND$3_GND$3") (pintype "bidirectional"))
    )
    (net (code "103") (name "unconnected-(U$6-PadGND$4)") (class "Default")
      (node (ref "U$6") (pin "GND$4") (pinfunction "GND$4_GND$4") (pintype "bidirectional"))
    )
    (net (code "104") (name "unconnected-(U$6-PadGND$5)") (class "Default")
      (node (ref "U$6") (pin "GND$5") (pinfunction "GND$5_GND$5") (pintype "bidirectional"))
    )
    (net (code "105") (name "unconnected-(U$6-PadGND$6)") (class "Default")
      (node (ref "U$6") (pin "GND$6") (pinfunction "GND$6_GND$6") (pintype "bidirectional"))
    )
  )
)
